# SK6812_Mini-E.net
KiCad netlist of a schematic drawn in Altium Designer
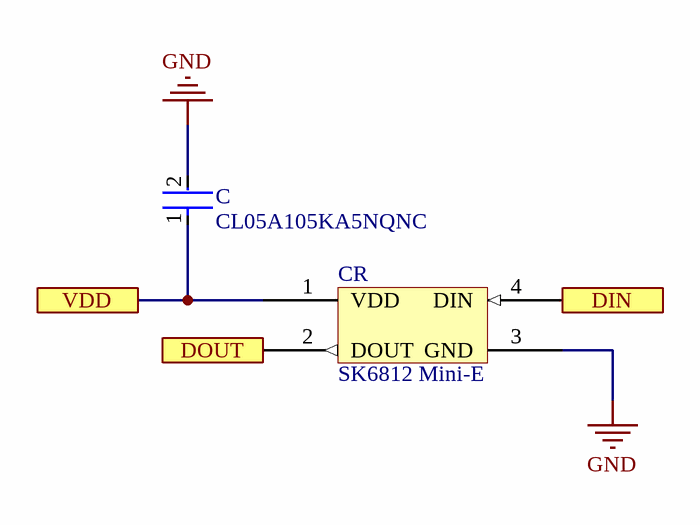
[diagram p0: SK6812 Mini-E.SchDoc]

(export (version "E")
  (design (tool "Eeschema 10.0.6"))
  (components
    (comp (ref "C")
      (value "CL05A105KA5NQNC")
      (footprint "FP-CL542-IPC_C")
      (description "Cap Ceramic 1uF 25V X5R ±10% SMD 0402 +85°C Paper T/R")
      (fields (field (name "TOLERANCE") "10%"))
      (libsource (lib "Altium Content Vault") (part "b4654b650e69147ec39a6b967a45e02"))
    )
    (comp (ref "CR")
      (value "SK6812 Mini-E")
      (footprint "SK6812 Mini-E")
      (description "Individually Adressable SK6812 Mini-E 3528 LED")
      (libsource (lib "Skayboard") (part "SK6812 Mini-E"))
    )
  )
  (nets
    (net (code "1") (name "/DIN") (class "Default")
      (node (ref "CR") (pin "4") (pinfunction "DIN_4") (pintype "input"))
    )
    (net (code "2") (name "/DOUT") (class "Default")
      (node (ref "CR") (pin "2") (pinfunction "DOUT_2") (pintype "output"))
    )
    (net (code "3") (name "/VDD") (class "Default")
      (node (ref "C") (pin "1") (pinfunction "1_1") (pintype "passive"))
      (node (ref "CR") (pin "1") (pinfunction "VDD_1") (pintype "power_in"))
    )
    (net (code "4") (name "GND") (class "Default")
      (node (ref "C") (pin "2") (pinfunction "2_2") (pintype "passive"))
      (node (ref "CR") (pin "3") (pinfunction "GND_3") (pintype "power_in"))
    )
  )
)
